# AIM2_-_WDT_REVB.net
KiCad netlist of a schematic drawn in Altium Designer
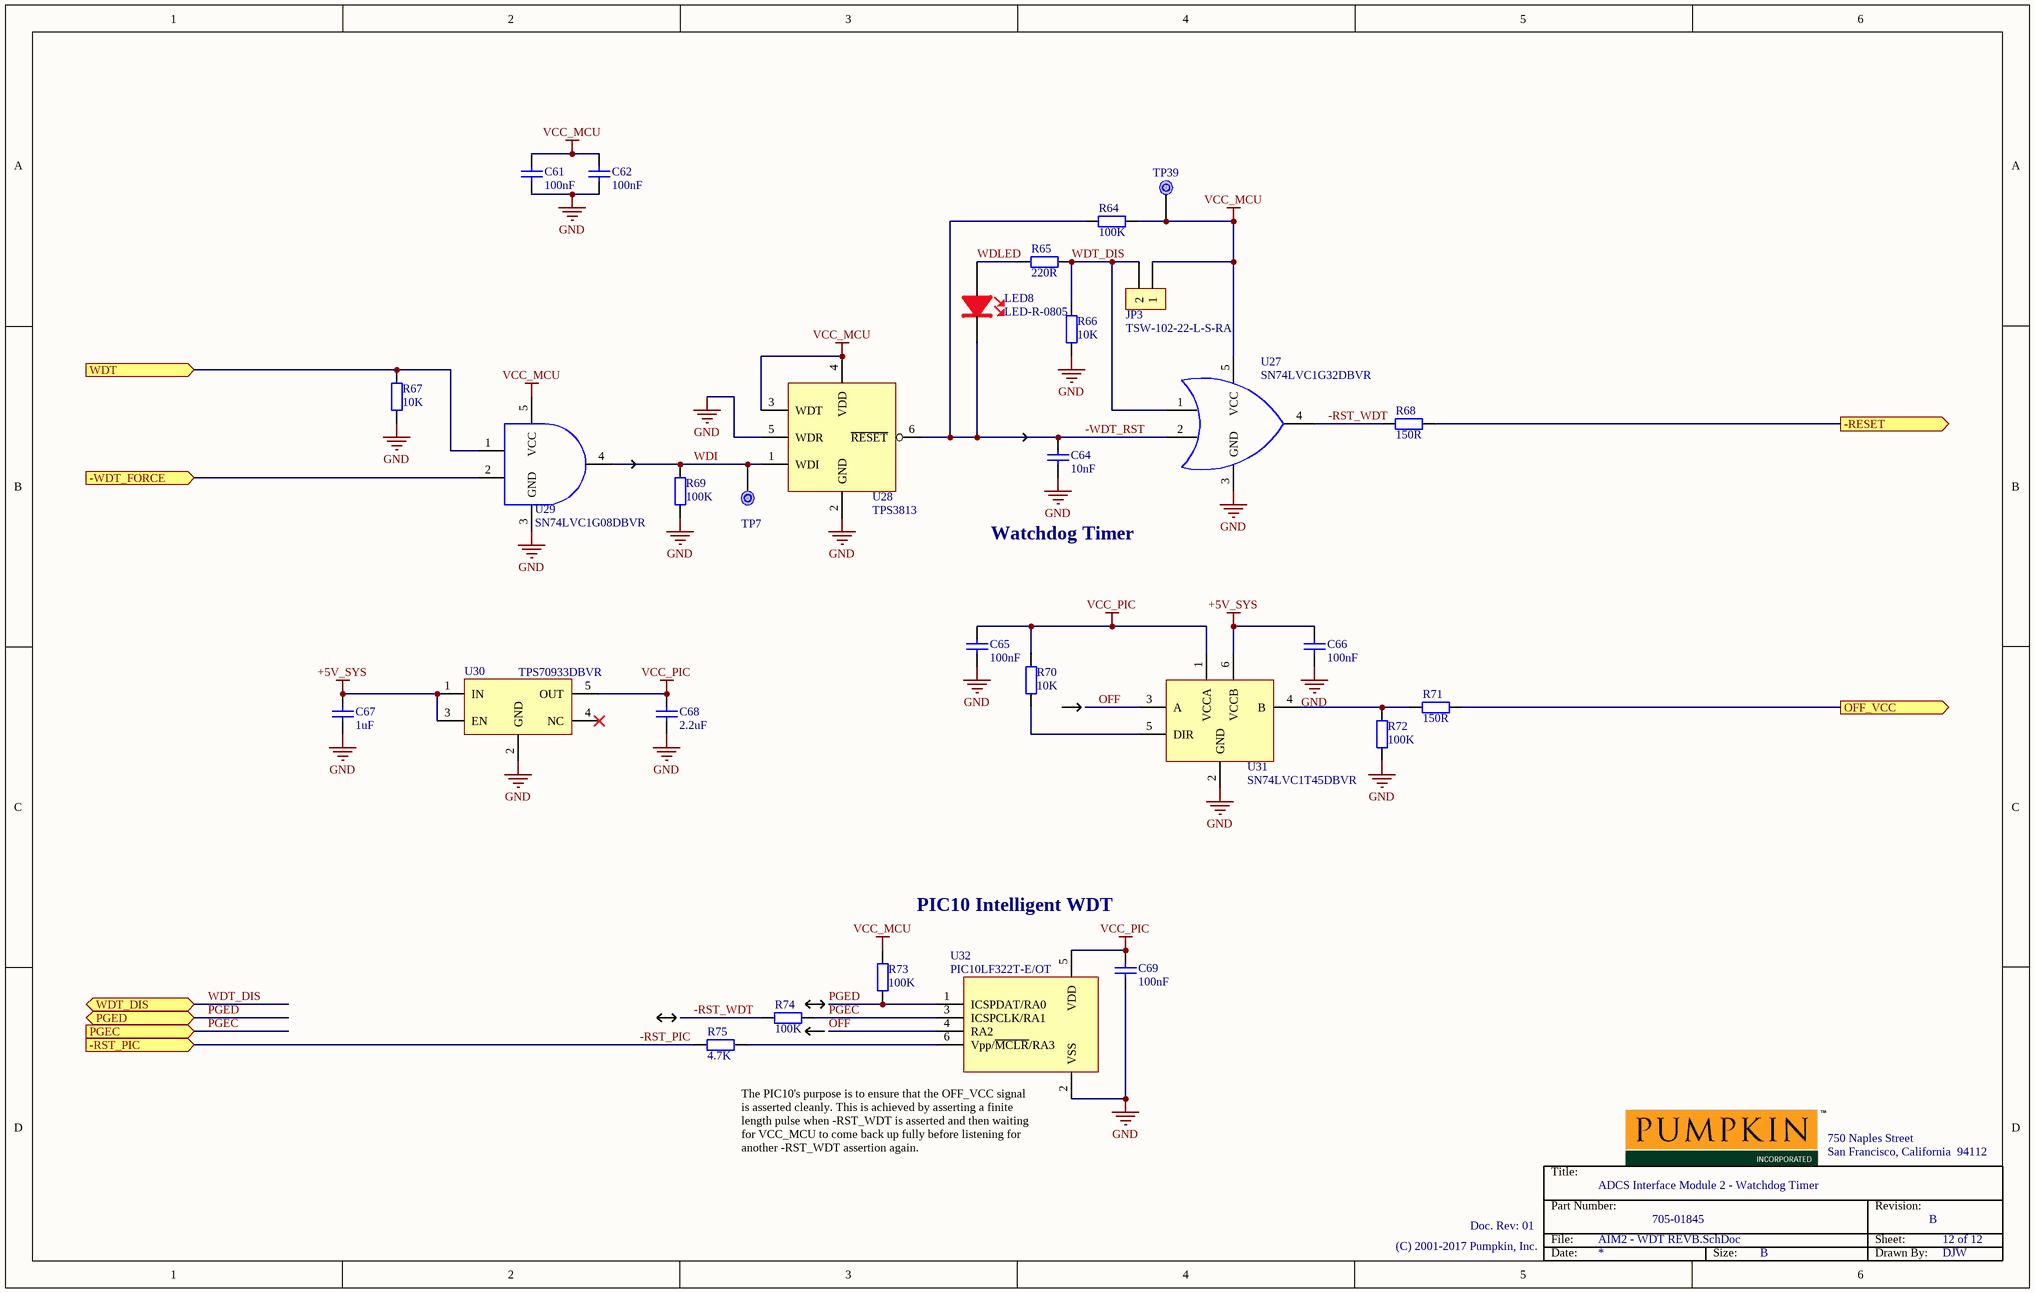
[diagram p0: AIM2 - WDT REVB.SchDoc]

(export (version "E")
  (design (tool "Eeschema 10.0.6"))
  (components
    (comp (ref "C61")
      (value "100nF")
      (footprint "0603 CAP")
      (description "Capacitor 100nF 0603 X7R 50V 5%")
      (libsource (lib "Supernova passives") (part "Capacitor 100nF 0603"))
    )
    (comp (ref "C62")
      (value "100nF")
      (footprint "0603 CAP")
      (description "Capacitor 100nF 0603 X7R 50V 5%")
      (libsource (lib "Supernova passives") (part "Capacitor 100nF 0603"))
    )
    (comp (ref "C64")
      (value "10nF")
      (footprint "0805 CAP")
      (description "Capacitor 10nF 0805 X7R 50V 5%")
      (libsource (lib "Supernova passives") (part "Capacitor 10nF 0805"))
    )
    (comp (ref "C65")
      (value "100nF")
      (footprint "0603 CAP")
      (description "Capacitor 100nF 0603 X7R 50V 5%")
      (libsource (lib "Supernova passives") (part "Capacitor 100nF 0603"))
    )
    (comp (ref "C66")
      (value "100nF")
      (footprint "0603 CAP")
      (description "Capacitor 100nF 0603 X7R 50V 5%")
      (libsource (lib "Supernova passives") (part "Capacitor 100nF 0603"))
    )
    (comp (ref "C67")
      (value "1uF")
      (footprint "0805 CAP")
      (description "Capacitor 1uF 0805 X7R 25V 10%")
      (libsource (lib "Supernova passives") (part "Capacitor 1uF 0805"))
    )
    (comp (ref "C68")
      (value "2.2uF")
      (footprint "0805 CAP")
      (description "Capacitor 2.2uF 0805 X7R 35V 10%")
      (libsource (lib "Supernova passives") (part "Capacitor 2.2uF 0805"))
    )
    (comp (ref "C69")
      (value "100nF")
      (footprint "0603 CAP")
      (description "Capacitor 100nF 0603 X7R 50V 5%")
      (libsource (lib "Supernova passives") (part "Capacitor 100nF 0603"))
    )
    (comp (ref "JP3")
      (value "TSW-102-22-L-S-RA")
      (footprint "TSW-102-22-L-S-RA")
      (description "Header 2x1 RA TH raised")
      (libsource (lib "Supernova") (part "TSW-102-22-L-S-RA"))
    )
    (comp (ref "LED8")
      (value "LED-R-0805")
      (footprint "0805 LED-RED")
      (description "LED Red 0805")
      (libsource (lib "Supernova passives") (part "LED RED 0805"))
    )
    (comp (ref "R64")
      (value "100K")
      (footprint "0805 RES")
      (description "Resistor 100K 0805 0.5W 1%")
      (libsource (lib "") (part "Resistor 100K 0805_1"))
    )
    (comp (ref "R65")
      (value "220R")
      (footprint "0805 RES")
      (description "Resistor 220R 0805 0.125W 1%")
      (libsource (lib "Supernova passives") (part "Resistor 220R 0805"))
    )
    (comp (ref "R66")
      (value "10K")
      (footprint "0805 RES")
      (description "Resistor 10K 0805 0.125W 1%")
      (libsource (lib "Supernova passives") (part "Resistor 10K 0805"))
    )
    (comp (ref "R67")
      (value "10K")
      (footprint "0805 RES")
      (description "Resistor 10K 0805 0.125W 1%")
      (libsource (lib "Supernova passives") (part "Resistor 10K 0805"))
    )
    (comp (ref "R68")
      (value "150R")
      (footprint "0805 RES")
      (description "Resistor 150R 0805 0.125W 1%")
      (libsource (lib "Supernova passives") (part "Resistor 150R 0805"))
    )
    (comp (ref "R69")
      (value "100K")
      (footprint "0805 RES")
      (description "Resistor 100K 0805 0.5W 1%")
      (libsource (lib "Supernova passives") (part "Resistor 100K 0805"))
    )
    (comp (ref "R70")
      (value "10K")
      (footprint "0805 RES")
      (description "Resistor 10K 0805 0.125W 1%")
      (libsource (lib "Supernova passives") (part "Resistor 10K 0805"))
    )
    (comp (ref "R71")
      (value "150R")
      (footprint "0805 RES")
      (description "Resistor 150R 0805 0.125W 1%")
      (libsource (lib "Supernova passives") (part "Resistor 150R 0805"))
    )
    (comp (ref "R72")
      (value "100K")
      (footprint "0805 RES")
      (description "Resistor 100K 0805 0.5W 1%")
      (libsource (lib "") (part "Resistor 100K 0805_3"))
    )
    (comp (ref "R73")
      (value "100K")
      (footprint "0805 RES")
      (description "Resistor 100K 0805 0.5W 1%")
      (libsource (lib "Supernova passives") (part "Resistor 100K 0805"))
    )
    (comp (ref "R74")
      (value "100K")
      (footprint "0805 RES")
      (description "Resistor 100K 0805 0.5W 1%")
      (libsource (lib "") (part "Resistor 100K 0805_2"))
    )
    (comp (ref "R75")
      (value "4.7K")
      (footprint "0805 RES")
      (description "Resistor 4.7K 0805 0.125W 1%")
      (libsource (lib "Supernova passives") (part "Resistor 4K7 0805"))
    )
    (comp (ref "TP7")
      (value "Testpoint")
      (footprint "Testpoint")
      (libsource (lib "Supernova") (part "Testpoint"))
    )
    (comp (ref "TP39")
      (value "Testpoint")
      (footprint "Testpoint")
      (libsource (lib "Supernova") (part "Testpoint"))
    )
    (comp (ref "U27")
      (value "SN74LVC1G32DBVR")
      (footprint "SOT23-5")
      (description "IC Logic OR 1 channel")
      (libsource (lib "Supernova") (part "SN74LVC1G32DBVR"))
    )
    (comp (ref "U28")
      (value "TPS3813")
      (footprint "SOT23-6")
      (description "IC Supervisor Watchdog")
      (libsource (lib "Supernova") (part "TPS3813"))
    )
    (comp (ref "U29")
      (value "SN74LVC1G08DBVR")
      (footprint "SOT23-5")
      (description "IC Logic AND 2 input")
      (libsource (lib "Supernova") (part "SN74LVC1G08DBVR"))
    )
    (comp (ref "U30")
      (value "TPS70933DBVR")
      (footprint "SOT23-5")
      (description "Regulator 3.3 V LDO")
      (libsource (lib "Supernova") (part "TPS70933"))
    )
    (comp (ref "U31")
      (value "SN74LVC1T45DBVR")
      (footprint "SOT23-6")
      (description "IC Logic Isolator 1 channel")
      (libsource (lib "Supernova") (part "SN74LVC1T45DBVR"))
    )
    (comp (ref "U32")
      (value "PIC10LF322T-E/OT")
      (footprint "SOT23-6")
      (description "IC Processor 8 bit")
      (libsource (lib "Supernova") (part "PIC10LF322T-E/OT"))
    )
  )
  (nets
    (net (code "1") (name "+5V_SYS") (class "Default")
      (node (ref "C66") (pin "2") (pinfunction "2_2") (pintype "passive"))
      (node (ref "C67") (pin "1") (pinfunction "1_1") (pintype "passive"))
      (node (ref "U30") (pin "1") (pinfunction "IN_1") (pintype "passive"))
      (node (ref "U30") (pin "3") (pinfunction "EN_3") (pintype "passive"))
      (node (ref "U31") (pin "6") (pinfunction "VCCB_6") (pintype "passive"))
    )
    (net (code "2") (name "/-RESET") (class "Default")
      (node (ref "R68") (pin "2") (pinfunction "2_2") (pintype "passive"))
    )
    (net (code "3") (name "/-RST_PIC") (class "Default")
      (node (ref "R75") (pin "2") (pinfunction "2_2") (pintype "passive"))
    )
    (net (code "4") (name "/-RST_WDT") (class "Default")
      (node (ref "R68") (pin "1") (pinfunction "1_1") (pintype "passive"))
      (node (ref "R74") (pin "1") (pinfunction "1_1") (pintype "passive"))
      (node (ref "U27") (pin "4") (pinfunction "A+B_4") (pintype "passive"))
    )
    (net (code "5") (name "/-WDT_FORCE") (class "Default")
      (node (ref "U29") (pin "2") (pinfunction "5_2") (pintype "passive"))
    )
    (net (code "6") (name "/-WDT_RST") (class "Default")
      (node (ref "C64") (pin "2") (pinfunction "2_2") (pintype "passive"))
      (node (ref "LED8") (pin "1") (pinfunction "1_1") (pintype "passive"))
      (node (ref "R64") (pin "2") (pinfunction "2_2") (pintype "passive"))
      (node (ref "U27") (pin "2") (pinfunction "1B_2") (pintype "passive"))
      (node (ref "U28") (pin "6") (pinfunction "~{RESET}_6") (pintype "passive"))
    )
    (net (code "7") (name "/OFF") (class "Default")
      (node (ref "U31") (pin "3") (pinfunction "A_3") (pintype "passive"))
      (node (ref "U32") (pin "4") (pinfunction "RA2_4") (pintype "passive"))
    )
    (net (code "8") (name "/OFF_VCC") (class "Default")
      (node (ref "R71") (pin "2") (pinfunction "2_2") (pintype "passive"))
    )
    (net (code "9") (name "/PGEC") (class "Default")
      (node (ref "R74") (pin "2") (pinfunction "2_2") (pintype "passive"))
      (node (ref "U32") (pin "3") (pinfunction "ICSPCLK/RA1_3") (pintype "passive"))
    )
    (net (code "10") (name "/PGED") (class "Default")
      (node (ref "R73") (pin "1") (pinfunction "1_1") (pintype "passive"))
      (node (ref "U32") (pin "1") (pinfunction "ICSPDAT/RA0_1") (pintype "passive"))
    )
    (net (code "11") (name "/WDI") (class "Default")
      (node (ref "R69") (pin "2") (pinfunction "2_2") (pintype "passive"))
      (node (ref "TP7") (pin "1") (pinfunction "1_1") (pintype "passive"))
      (node (ref "U28") (pin "1") (pinfunction "WDI_1") (pintype "passive"))
      (node (ref "U29") (pin "4") (pinfunction "11_4") (pintype "passive"))
    )
    (net (code "12") (name "/WDLED") (class "Default")
      (node (ref "LED8") (pin "2") (pinfunction "2_2") (pintype "passive"))
      (node (ref "R65") (pin "1") (pinfunction "1_1") (pintype "passive"))
    )
    (net (code "13") (name "/WDT") (class "Default")
      (node (ref "R67") (pin "2") (pinfunction "2_2") (pintype "passive"))
      (node (ref "U29") (pin "1") (pinfunction "5_1") (pintype "passive"))
    )
    (net (code "14") (name "/WDT_DIS") (class "Default")
      (node (ref "JP3") (pin "2") (pinfunction "2_2") (pintype "passive"))
      (node (ref "R65") (pin "2") (pinfunction "2_2") (pintype "passive"))
      (node (ref "R66") (pin "2") (pinfunction "2_2") (pintype "passive"))
      (node (ref "U27") (pin "1") (pinfunction "1A_1") (pintype "passive"))
    )
    (net (code "15") (name "GND") (class "Default")
      (node (ref "C61") (pin "1") (pinfunction "1_1") (pintype "passive"))
      (node (ref "C62") (pin "1") (pinfunction "1_1") (pintype "passive"))
      (node (ref "C64") (pin "1") (pinfunction "1_1") (pintype "passive"))
      (node (ref "C65") (pin "1") (pinfunction "1_1") (pintype "passive"))
      (node (ref "C66") (pin "1") (pinfunction "1_1") (pintype "passive"))
      (node (ref "C67") (pin "2") (pinfunction "2_2") (pintype "passive"))
      (node (ref "C68") (pin "1") (pinfunction "1_1") (pintype "passive"))
      (node (ref "C69") (pin "1") (pinfunction "1_1") (pintype "passive"))
      (node (ref "R66") (pin "1") (pinfunction "1_1") (pintype "passive"))
      (node (ref "R67") (pin "1") (pinfunction "1_1") (pintype "passive"))
      (node (ref "R69") (pin "1") (pinfunction "1_1") (pintype "passive"))
      (node (ref "R72") (pin "2") (pinfunction "2_2") (pintype "passive"))
      (node (ref "U27") (pin "3") (pinfunction "GND_3") (pintype "passive"))
      (node (ref "U28") (pin "2") (pinfunction "GND_2") (pintype "power_in"))
      (node (ref "U28") (pin "5") (pinfunction "WDR_5") (pintype "passive"))
      (node (ref "U29") (pin "3") (pinfunction "GND_3") (pintype "passive"))
      (node (ref "U30") (pin "2") (pinfunction "GND_2") (pintype "passive"))
      (node (ref "U31") (pin "2") (pinfunction "GND_2") (pintype "passive"))
      (node (ref "U32") (pin "2") (pinfunction "VSS_2") (pintype "passive"))
    )
    (net (code "16") (name "Net-(U31-B)") (class "Default")
      (node (ref "R71") (pin "1") (pinfunction "1_1") (pintype "passive"))
      (node (ref "R72") (pin "1") (pinfunction "1_1") (pintype "passive"))
      (node (ref "U31") (pin "4") (pinfunction "B_4") (pintype "passive"))
    )
    (net (code "17") (name "Net-(U31-DIR)") (class "Default")
      (node (ref "R70") (pin "1") (pinfunction "1_1") (pintype "passive"))
      (node (ref "U31") (pin "5") (pinfunction "DIR_5") (pintype "passive"))
    )
    (net (code "18") (name "Net-(U32-Vpp{slash}~{MCLR}{slash}RA3)") (class "Default")
      (node (ref "R75") (pin "1") (pinfunction "1_1") (pintype "passive"))
      (node (ref "U32") (pin "6") (pinfunction "Vpp/~{MCLR}/RA3_6") (pintype "passive"))
    )
    (net (code "19") (name "VCC_MCU") (class "Default")
      (node (ref "C61") (pin "2") (pinfunction "2_2") (pintype "passive"))
      (node (ref "C62") (pin "2") (pinfunction "2_2") (pintype "passive"))
      (node (ref "JP3") (pin "1") (pinfunction "1_1") (pintype "passive"))
      (node (ref "R64") (pin "1") (pinfunction "1_1") (pintype "passive"))
      (node (ref "R73") (pin "2") (pinfunction "2_2") (pintype "passive"))
      (node (ref "TP39") (pin "1") (pinfunction "1_1") (pintype "passive"))
      (node (ref "U27") (pin "5") (pinfunction "VCC_5") (pintype "passive"))
      (node (ref "U28") (pin "3") (pinfunction "WDT_3") (pintype "passive"))
      (node (ref "U28") (pin "4") (pinfunction "VDD_4") (pintype "power_in"))
      (node (ref "U29") (pin "5") (pinfunction "VCC_5") (pintype "passive"))
    )
    (net (code "20") (name "VCC_PIC") (class "Default")
      (node (ref "C65") (pin "2") (pinfunction "2_2") (pintype "passive"))
      (node (ref "C68") (pin "2") (pinfunction "2_2") (pintype "passive"))
      (node (ref "C69") (pin "2") (pinfunction "2_2") (pintype "passive"))
      (node (ref "R70") (pin "2") (pinfunction "2_2") (pintype "passive"))
      (node (ref "U30") (pin "5") (pinfunction "OUT_5") (pintype "passive"))
      (node (ref "U31") (pin "1") (pinfunction "VCCA_1") (pintype "passive"))
      (node (ref "U32") (pin "5") (pinfunction "VDD_5") (pintype "passive"))
    )
    (net (code "21") (name "unconnected-(U30-NC-Pad4)") (class "Default")
      (node (ref "U30") (pin "4") (pinfunction "NC_4") (pintype "passive+no_connect"))
    )
  )
)
